# LDO.net
KiCad netlist of a schematic drawn in Altium Designer
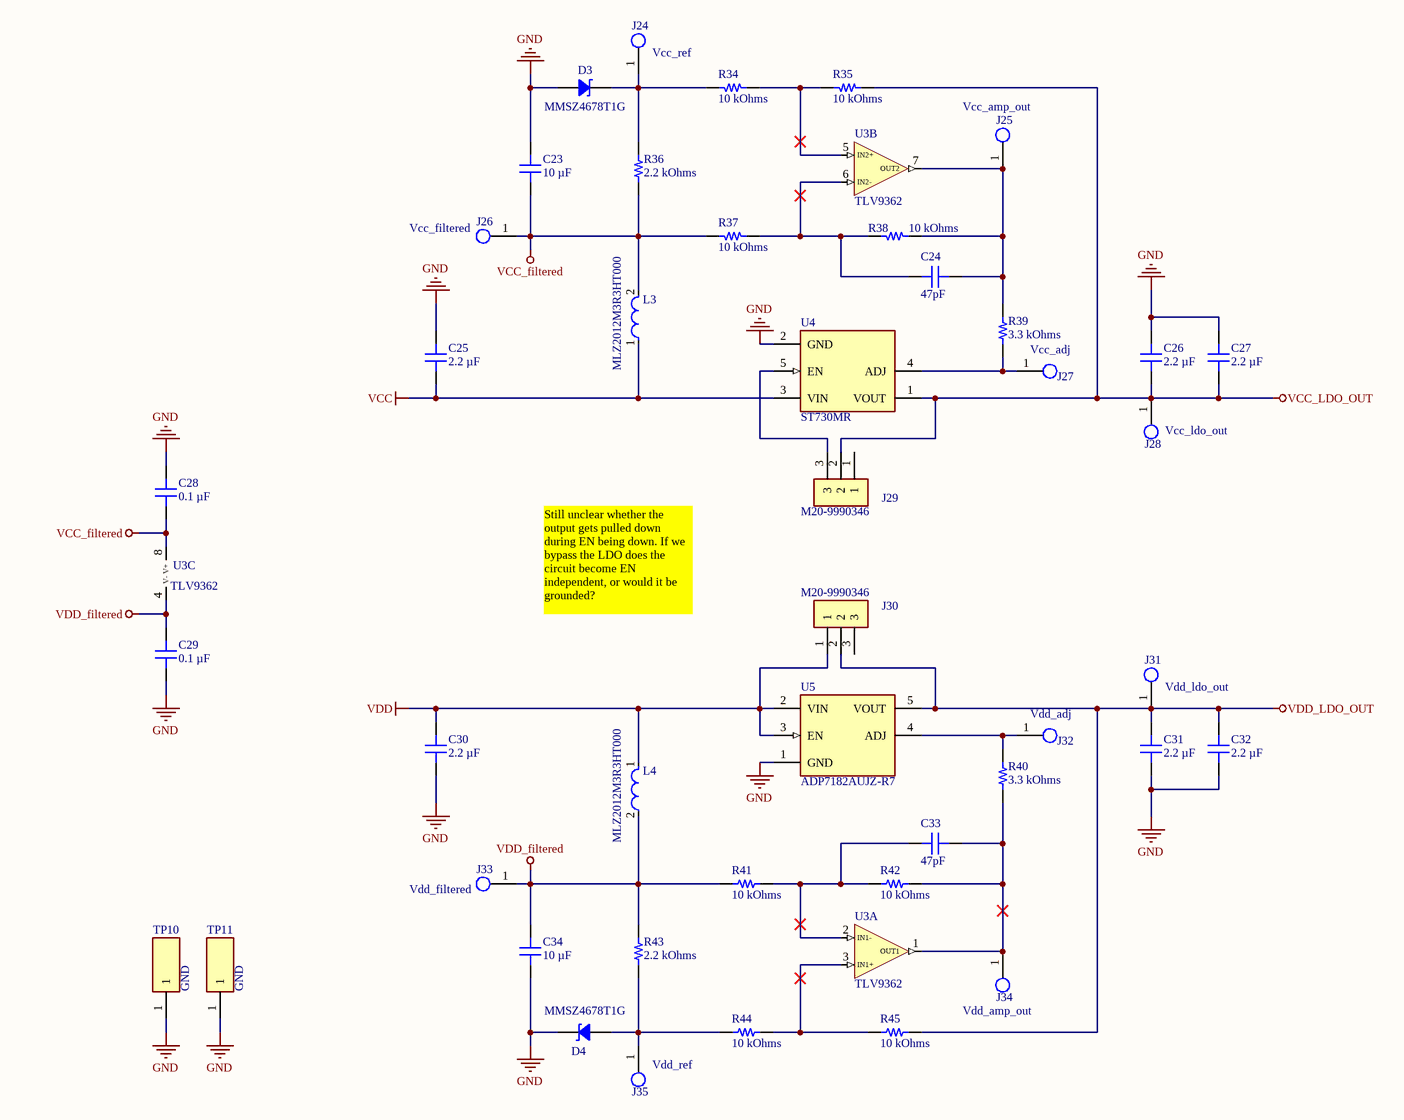
[diagram p0: LDO.SchDoc]

(export (version "E")
  (design (tool "Eeschema 10.0.6"))
  (components
    (comp (ref "C23")
      (value "10 µF")
      (footprint "CAP 1206_3216 - 0.8MM")
      (description "CAP CER 10UF 25V X7R 1206")
      (fields
        (field (name "PART NUMBER") "885012208069")
        (field (name "CAPACITANCE") "10 µF")
        (field (name "MANUFACTURER") "Würth Elektronik")
      )
      (libsource (lib "Celestial Altium Library - altium_library") (part "Capacitor"))
    )
    (comp (ref "C24")
      (value "47pF")
      (footprint "CAP 1206_3216 - 1.8MM")
      (description "CAP CER 47PF 1KV C0G/NP0 1206")
      (fields
        (field (name "PART NUMBER") "1206AA470KAT1A")
        (field (name "CAPACITANCE") "47pF")
        (field (name "MANUFACTURER") "AVX Corporation")
      )
      (libsource (lib "Celestial Altium Library - altium_library") (part "Capacitor"))
    )
    (comp (ref "C25")
      (value "2.2 µF")
      (footprint "CAP 1206_3216 - 0.8MM")
      (description "CAP CER 2.2UF 25V X7R 1206")
      (fields
        (field (name "PART NUMBER") "885382208001")
        (field (name "CAPACITANCE") "2.2 µF")
        (field (name "MANUFACTURER") "Würth Elektronik")
      )
      (libsource (lib "Celestial Altium Library - altium_library") (part "Capacitor"))
    )
    (comp (ref "C26")
      (value "2.2 µF")
      (footprint "CAP 1206_3216 - 0.8MM")
      (description "CAP CER 2.2UF 25V X7R 1206")
      (fields
        (field (name "PART NUMBER") "885382208001")
        (field (name "CAPACITANCE") "2.2 µF")
        (field (name "MANUFACTURER") "Würth Elektronik")
      )
      (libsource (lib "Celestial Altium Library - altium_library") (part "Capacitor"))
    )
    (comp (ref "C27")
      (value "2.2 µF")
      (footprint "CAP 1206_3216 - 0.8MM")
      (description "CAP CER 2.2UF 25V X7R 1206")
      (fields
        (field (name "PART NUMBER") "885382208001")
        (field (name "CAPACITANCE") "2.2 µF")
        (field (name "MANUFACTURER") "Würth Elektronik")
      )
      (libsource (lib "Celestial Altium Library - altium_library") (part "Capacitor"))
    )
    (comp (ref "C28")
      (value "0.1 µF")
      (footprint "CAP 1206_3216 - 0.8MM")
      (description "CAP CER 0.1UF 50V X7R 1206")
      (fields
        (field (name "PART NUMBER") "885012208087")
        (field (name "CAPACITANCE") "0.1 µF")
        (field (name "MANUFACTURER") "Würth Elektronik")
      )
      (libsource (lib "Celestial Altium Library - altium_library") (part "Capacitor"))
    )
    (comp (ref "C29")
      (value "0.1 µF")
      (footprint "CAP 1206_3216 - 0.8MM")
      (description "CAP CER 0.1UF 50V X7R 1206")
      (fields
        (field (name "PART NUMBER") "885012208087")
        (field (name "CAPACITANCE") "0.1 µF")
        (field (name "MANUFACTURER") "Würth Elektronik")
      )
      (libsource (lib "Celestial Altium Library - altium_library") (part "Capacitor"))
    )
    (comp (ref "C30")
      (value "2.2 µF")
      (footprint "CAP 1206_3216 - 0.8MM")
      (description "CAP CER 2.2UF 25V X7R 1206")
      (fields
        (field (name "PART NUMBER") "885382208001")
        (field (name "CAPACITANCE") "2.2 µF")
        (field (name "MANUFACTURER") "Würth Elektronik")
      )
      (libsource (lib "Celestial Altium Library - altium_library") (part "Capacitor"))
    )
    (comp (ref "C31")
      (value "2.2 µF")
      (footprint "CAP 1206_3216 - 0.8MM")
      (description "CAP CER 2.2UF 25V X7R 1206")
      (fields
        (field (name "PART NUMBER") "885382208001")
        (field (name "CAPACITANCE") "2.2 µF")
        (field (name "MANUFACTURER") "Würth Elektronik")
      )
      (libsource (lib "Celestial Altium Library - altium_library") (part "Capacitor"))
    )
    (comp (ref "C32")
      (value "2.2 µF")
      (footprint "CAP 1206_3216 - 0.8MM")
      (description "CAP CER 2.2UF 25V X7R 1206")
      (fields
        (field (name "PART NUMBER") "885382208001")
        (field (name "CAPACITANCE") "2.2 µF")
        (field (name "MANUFACTURER") "Würth Elektronik")
      )
      (libsource (lib "Celestial Altium Library - altium_library") (part "Capacitor"))
    )
    (comp (ref "C33")
      (value "47pF")
      (footprint "CAP 1206_3216 - 1.8MM")
      (description "CAP CER 47PF 1KV C0G/NP0 1206")
      (fields
        (field (name "PART NUMBER") "1206AA470KAT1A")
        (field (name "CAPACITANCE") "47pF")
        (field (name "MANUFACTURER") "AVX Corporation")
      )
      (libsource (lib "Celestial Altium Library - altium_library") (part "Capacitor"))
    )
    (comp (ref "C34")
      (value "10 µF")
      (footprint "CAP 1206_3216 - 0.8MM")
      (description "CAP CER 10UF 25V X7R 1206")
      (fields
        (field (name "PART NUMBER") "885012208069")
        (field (name "CAPACITANCE") "10 µF")
        (field (name "MANUFACTURER") "Würth Elektronik")
      )
      (libsource (lib "Celestial Altium Library - altium_library") (part "Capacitor"))
    )
    (comp (ref "D3")
      (value "MMSZ4678T1G")
      (footprint "SOD3716X135N")
      (description "Zener Diode")
      (fields (field (name "MOUSER PART NUMBER") "863-MMSZ4678T1G"))
      (libsource (lib "za_koncar") (part "MMSZ4678T1G"))
    )
    (comp (ref "D4")
      (value "MMSZ4678T1G")
      (footprint "SOD3716X135N")
      (description "Zener Diode")
      (fields (field (name "MOUSER PART NUMBER") "863-MMSZ4678T1G"))
      (libsource (lib "za_koncar") (part "MMSZ4678T1G"))
    )
    (comp (ref "J24")
      (value "Vcc_ref")
      (footprint "FP-5001-MFG")
      (description "PC TEST POINT MINIATURE BLACK")
      (libsource (lib "za_koncar") (part "5001"))
    )
    (comp (ref "J25")
      (value "Vcc_amp_out")
      (footprint "FP-5001-MFG")
      (description "PC TEST POINT MINIATURE BLACK")
      (libsource (lib "za_koncar") (part "5001"))
    )
    (comp (ref "J26")
      (value "Vcc_filtered")
      (footprint "FP-5001-MFG")
      (description "PC TEST POINT MINIATURE BLACK")
      (libsource (lib "za_koncar") (part "5001"))
    )
    (comp (ref "J27")
      (value "Vcc_adj")
      (footprint "FP-5001-MFG")
      (description "PC TEST POINT MINIATURE BLACK")
      (libsource (lib "za_koncar") (part "5001"))
    )
    (comp (ref "J28")
      (value "Vcc_ldo_out")
      (footprint "FP-5001-MFG")
      (description "PC TEST POINT MINIATURE BLACK")
      (libsource (lib "za_koncar") (part "5001"))
    )
    (comp (ref "J29")
      (value "M20-9990346")
      (footprint "HDRV3W64P0X254_1X3_762X254X864P - duplicate")
      (description "Connector")
      (fields (field (name "MOUSER PART NUMBER") "855-M20-9990346"))
      (libsource (lib "za_koncar") (part "M20-9990346"))
    )
    (comp (ref "J30")
      (value "M20-9990346")
      (footprint "HDRV3W64P0X254_1X3_762X254X864P - duplicate")
      (description "Connector")
      (fields (field (name "MOUSER PART NUMBER") "855-M20-9990346"))
      (libsource (lib "") (part "M20-9990346_1"))
    )
    (comp (ref "J31")
      (value "Vdd_ldo_out")
      (footprint "FP-5001-MFG")
      (description "PC TEST POINT MINIATURE BLACK")
      (libsource (lib "za_koncar") (part "5001"))
    )
    (comp (ref "J32")
      (value "Vdd_adj")
      (footprint "FP-5001-MFG")
      (description "PC TEST POINT MINIATURE BLACK")
      (libsource (lib "za_koncar") (part "5001"))
    )
    (comp (ref "J33")
      (value "Vdd_filtered")
      (footprint "FP-5001-MFG")
      (description "PC TEST POINT MINIATURE BLACK")
      (libsource (lib "za_koncar") (part "5001"))
    )
    (comp (ref "J34")
      (value "Vdd_amp_out")
      (footprint "FP-5001-MFG")
      (description "PC TEST POINT MINIATURE BLACK")
      (libsource (lib "za_koncar") (part "5001"))
    )
    (comp (ref "J35")
      (value "Vdd_ref")
      (footprint "FP-5001-MFG")
      (description "PC TEST POINT MINIATURE BLACK")
      (libsource (lib "za_koncar") (part "5001"))
    )
    (comp (ref "L3")
      (value "MLZ2012M3R3HT000")
      (footprint "FP-MLZ2012-1_25-IPC_B")
      (description "Shielded Multilayer Inductor 3.3uH ±20% 500mA 260mΩ SMD 0805")
      (fields (field (name "TOLERANCE") "20%"))
      (libsource (lib "za_koncar") (part "MLZ2012M3R3HT000"))
    )
    (comp (ref "L4")
      (value "MLZ2012M3R3HT000")
      (footprint "FP-MLZ2012-1_25-IPC_B")
      (description "Shielded Multilayer Inductor 3.3uH ±20% 500mA 260mΩ SMD 0805")
      (fields (field (name "TOLERANCE") "20%"))
      (libsource (lib "") (part "MLZ2012M3R3HT000_1"))
    )
    (comp (ref "R34")
      (value "10 kOhms")
      (footprint "YAGEO RES 1206_3216")
      (description "RES SMD 10K OHM 1% 1/4W 1206")
      (fields (field (name "PART NUMBER") "RT1206FRE0710KL") (field (name "MANUFACTURER") "Yageo"))
      (libsource (lib "Celestial Altium Library - altium_library") (part "Resistor"))
    )
    (comp (ref "R35")
      (value "10 kOhms")
      (footprint "YAGEO RES 1206_3216")
      (description "RES SMD 10K OHM 1% 1/4W 1206")
      (fields (field (name "PART NUMBER") "RT1206FRE0710KL") (field (name "MANUFACTURER") "Yageo"))
      (libsource (lib "Celestial Altium Library - altium_library") (part "Resistor"))
    )
    (comp (ref "R36")
      (value "2.2 kOhms")
      (footprint "YAGEO RES 1206_3216")
      (description "RES SMD 2.2K OHM 1% 1/4W 1206")
      (fields (field (name "PART NUMBER") "RT1206FRE072K2L") (field (name "MANUFACTURER") "Yageo"))
      (libsource (lib "Celestial Altium Library - altium_library") (part "Resistor"))
    )
    (comp (ref "R37")
      (value "10 kOhms")
      (footprint "YAGEO RES 1206_3216")
      (description "RES SMD 10K OHM 1% 1/4W 1206")
      (fields (field (name "PART NUMBER") "RT1206FRE0710KL") (field (name "MANUFACTURER") "Yageo"))
      (libsource (lib "Celestial Altium Library - altium_library") (part "Resistor"))
    )
    (comp (ref "R38")
      (value "10 kOhms")
      (footprint "YAGEO RES 1206_3216")
      (description "RES SMD 10K OHM 1% 1/4W 1206")
      (fields (field (name "PART NUMBER") "RT1206FRE0710KL") (field (name "MANUFACTURER") "Yageo"))
      (libsource (lib "Celestial Altium Library - altium_library") (part "Resistor"))
    )
    (comp (ref "R39")
      (value "3.3 kOhms")
      (footprint "YAGEO RES 1206_3216")
      (description "RES SMD 3.3K OHM 1% 1/4W 1206")
      (fields (field (name "PART NUMBER") "RT1206FRE073K3L") (field (name "MANUFACTURER") "Yageo"))
      (libsource (lib "Celestial Altium Library - altium_library") (part "Resistor"))
    )
    (comp (ref "R40")
      (value "3.3 kOhms")
      (footprint "YAGEO RES 1206_3216")
      (description "RES SMD 3.3K OHM 1% 1/4W 1206")
      (fields (field (name "PART NUMBER") "RT1206FRE073K3L") (field (name "MANUFACTURER") "Yageo"))
      (libsource (lib "Celestial Altium Library - altium_library") (part "Resistor"))
    )
    (comp (ref "R41")
      (value "10 kOhms")
      (footprint "YAGEO RES 1206_3216")
      (description "RES SMD 10K OHM 1% 1/4W 1206")
      (fields (field (name "PART NUMBER") "RT1206FRE0710KL") (field (name "MANUFACTURER") "Yageo"))
      (libsource (lib "Celestial Altium Library - altium_library") (part "Resistor"))
    )
    (comp (ref "R42")
      (value "10 kOhms")
      (footprint "YAGEO RES 1206_3216")
      (description "RES SMD 10K OHM 1% 1/4W 1206")
      (fields (field (name "PART NUMBER") "RT1206FRE0710KL") (field (name "MANUFACTURER") "Yageo"))
      (libsource (lib "Celestial Altium Library - altium_library") (part "Resistor"))
    )
    (comp (ref "R43")
      (value "2.2 kOhms")
      (footprint "YAGEO RES 1206_3216")
      (description "RES SMD 2.2K OHM 1% 1/4W 1206")
      (fields (field (name "PART NUMBER") "RT1206FRE072K2L") (field (name "MANUFACTURER") "Yageo"))
      (libsource (lib "Celestial Altium Library - altium_library") (part "Resistor"))
    )
    (comp (ref "R44")
      (value "10 kOhms")
      (footprint "YAGEO RES 1206_3216")
      (description "RES SMD 10K OHM 1% 1/4W 1206")
      (fields (field (name "PART NUMBER") "RT1206FRE0710KL") (field (name "MANUFACTURER") "Yageo"))
      (libsource (lib "Celestial Altium Library - altium_library") (part "Resistor"))
    )
    (comp (ref "R45")
      (value "10 kOhms")
      (footprint "YAGEO RES 1206_3216")
      (description "RES SMD 10K OHM 1% 1/4W 1206")
      (fields (field (name "PART NUMBER") "RT1206FRE0710KL") (field (name "MANUFACTURER") "Yageo"))
      (libsource (lib "Celestial Altium Library - altium_library") (part "Resistor"))
    )
    (comp (ref "TP10")
      (value "GND")
      (footprint "za_koncar:S175146R")
      (description "Test Point")
      (fields
        (field (name "MANUFACTURER_PART_NUMBER") "S1751-46R")
        (field (name "MOUSER PART NUMBER") "855-S1751-46R")
      )
      (libsource (lib "za_koncar") (part "S1751-46R"))
    )
    (comp (ref "TP11")
      (value "GND")
      (footprint "za_koncar:S175146R")
      (description "Test Point")
      (fields
        (field (name "MANUFACTURER_PART_NUMBER") "S1751-46R")
        (field (name "MOUSER PART NUMBER") "855-S1751-46R")
      )
      (libsource (lib "za_koncar") (part "S1751-46R"))
    )
    (comp (ref "U3")
      (value "TLV9362")
      (footprint "SOIC8-127P600X175-8N")
      (description "TLV936x 10-MHz, 40-V, RRO, Operational Amplifie")
      (libsource (lib "za_koncar") (part "TLV9362"))
    )
    (comp (ref "U4")
      (value "ST730MR")
      (footprint "FP-UJ-5-IPC_B")
      (libsource (lib "za_koncar") (part "ST730MR"))
    )
    (comp (ref "U5")
      (value "ADP7182AUJZ-R7")
      (footprint "FP-UJ-5-IPC_B")
      (description "IC REG LIN NEG ADJ 200MA 5TSOT")
      (fields
        (field (name "MANUFACTURER") "Analog Devices")
        (field (name "OCTOPART") "https://octopart.com/adp7182aujz-r7-analog+devices-21054665")
      )
      (libsource (lib "za_koncar") (part "ADP7182"))
    )
  )
  (nets
    (net (code "1") (name "GND") (class "Default")
      (node (ref "C23") (pin "1") (pinfunction "1_1") (pintype "passive"))
      (node (ref "C25") (pin "1") (pinfunction "1_1") (pintype "passive"))
      (node (ref "C26") (pin "1") (pinfunction "1_1") (pintype "passive"))
      (node (ref "C27") (pin "1") (pinfunction "1_1") (pintype "passive"))
      (node (ref "C28") (pin "2") (pinfunction "2_2") (pintype "passive"))
      (node (ref "C29") (pin "1") (pinfunction "1_1") (pintype "passive"))
      (node (ref "C30") (pin "1") (pinfunction "1_1") (pintype "passive"))
      (node (ref "C31") (pin "1") (pinfunction "1_1") (pintype "passive"))
      (node (ref "C32") (pin "1") (pinfunction "1_1") (pintype "passive"))
      (node (ref "C34") (pin "1") (pinfunction "1_1") (pintype "passive"))
      (node (ref "D3") (pin "1") (pinfunction "1_1") (pintype "passive"))
      (node (ref "D4") (pin "2") (pinfunction "2_2") (pintype "passive"))
      (node (ref "TP10") (pin "1") (pinfunction "1_1") (pintype "passive"))
      (node (ref "TP11") (pin "1") (pinfunction "1_1") (pintype "passive"))
      (node (ref "U4") (pin "2") (pinfunction "GND_2") (pintype "power_in"))
      (node (ref "U5") (pin "1") (pinfunction "GND_1") (pintype "power_in"))
    )
    (net (code "2") (name "Net-(D3-Pad2)") (class "Default")
      (node (ref "D3") (pin "2") (pinfunction "2_2") (pintype "passive"))
      (node (ref "J24") (pin "1") (pinfunction "1_1") (pintype "passive"))
      (node (ref "R34") (pin "2") (pinfunction "2_2") (pintype "passive"))
      (node (ref "R36") (pin "2") (pinfunction "2_2") (pintype "passive"))
    )
    (net (code "3") (name "Net-(D4-Pad1)") (class "Default")
      (node (ref "D4") (pin "1") (pinfunction "1_1") (pintype "passive"))
      (node (ref "J35") (pin "1") (pinfunction "1_1") (pintype "passive"))
      (node (ref "R43") (pin "1") (pinfunction "1_1") (pintype "passive"))
      (node (ref "R44") (pin "2") (pinfunction "2_2") (pintype "passive"))
    )
    (net (code "4") (name "Net-(U3A-IN1+)") (class "Default")
      (node (ref "R44") (pin "1") (pinfunction "1_1") (pintype "passive"))
      (node (ref "R45") (pin "2") (pinfunction "2_2") (pintype "passive"))
      (node (ref "U3") (pin "3") (pinfunction "IN1+_3") (pintype "input"))
    )
    (net (code "5") (name "Net-(U3A-IN1-)") (class "Default")
      (node (ref "C33") (pin "1") (pinfunction "1_1") (pintype "passive"))
      (node (ref "R41") (pin "1") (pinfunction "1_1") (pintype "passive"))
      (node (ref "R42") (pin "2") (pinfunction "2_2") (pintype "passive"))
      (node (ref "U3") (pin "2") (pinfunction "IN1-_2") (pintype "input"))
    )
    (net (code "6") (name "Net-(U3A-OUT1)") (class "Default")
      (node (ref "C33") (pin "2") (pinfunction "2_2") (pintype "passive"))
      (node (ref "J34") (pin "1") (pinfunction "1_1") (pintype "passive"))
      (node (ref "R40") (pin "2") (pinfunction "2_2") (pintype "passive"))
      (node (ref "R42") (pin "1") (pinfunction "1_1") (pintype "passive"))
      (node (ref "U3") (pin "1") (pinfunction "OUT1_1") (pintype "output"))
    )
    (net (code "7") (name "Net-(U3B-IN2+)") (class "Default")
      (node (ref "R34") (pin "1") (pinfunction "1_1") (pintype "passive"))
      (node (ref "R35") (pin "2") (pinfunction "2_2") (pintype "passive"))
      (node (ref "U3") (pin "5") (pinfunction "IN2+_5") (pintype "input"))
    )
    (net (code "8") (name "Net-(U3B-IN2-)") (class "Default")
      (node (ref "C24") (pin "1") (pinfunction "1_1") (pintype "passive"))
      (node (ref "R37") (pin "1") (pinfunction "1_1") (pintype "passive"))
      (node (ref "R38") (pin "2") (pinfunction "2_2") (pintype "passive"))
      (node (ref "U3") (pin "6") (pinfunction "IN2-_6") (pintype "input"))
    )
    (net (code "9") (name "Net-(U3B-OUT2)") (class "Default")
      (node (ref "C24") (pin "2") (pinfunction "2_2") (pintype "passive"))
      (node (ref "J25") (pin "1") (pinfunction "1_1") (pintype "passive"))
      (node (ref "R38") (pin "1") (pinfunction "1_1") (pintype "passive"))
      (node (ref "R39") (pin "1") (pinfunction "1_1") (pintype "passive"))
      (node (ref "U3") (pin "7") (pinfunction "OUT2_7") (pintype "output"))
    )
    (net (code "10") (name "Net-(U4-ADJ)") (class "Default")
      (node (ref "J27") (pin "1") (pinfunction "1_1") (pintype "passive"))
      (node (ref "R39") (pin "2") (pinfunction "2_2") (pintype "passive"))
      (node (ref "U4") (pin "4") (pinfunction "ADJ_4") (pintype "passive"))
    )
    (net (code "11") (name "Net-(U4-EN)") (class "Default")
      (node (ref "J29") (pin "3") (pinfunction "3_3") (pintype "passive"))
      (node (ref "U4") (pin "5") (pinfunction "EN_5") (pintype "input"))
    )
    (net (code "12") (name "Net-(U5-ADJ)") (class "Default")
      (node (ref "J32") (pin "1") (pinfunction "1_1") (pintype "passive"))
      (node (ref "R40") (pin "1") (pinfunction "1_1") (pintype "passive"))
      (node (ref "U5") (pin "4") (pinfunction "ADJ_4") (pintype "passive"))
    )
    (net (code "13") (name "VCC") (class "Default")
      (node (ref "C25") (pin "2") (pinfunction "2_2") (pintype "passive"))
      (node (ref "L3") (pin "1") (pinfunction "1_1") (pintype "passive"))
      (node (ref "U4") (pin "3") (pinfunction "VIN_3") (pintype "power_in"))
    )
    (net (code "14") (name "VCC_LDO_OUT") (class "Default")
      (node (ref "C26") (pin "2") (pinfunction "2_2") (pintype "passive"))
      (node (ref "C27") (pin "2") (pinfunction "2_2") (pintype "passive"))
      (node (ref "J28") (pin "1") (pinfunction "1_1") (pintype "passive"))
      (node (ref "J29") (pin "2") (pinfunction "2_2") (pintype "passive"))
      (node (ref "R35") (pin "1") (pinfunction "1_1") (pintype "passive"))
      (node (ref "U4") (pin "1") (pinfunction "VOUT_1") (pintype "power_in"))
    )
    (net (code "15") (name "VCC_filtered") (class "Default")
      (node (ref "C23") (pin "2") (pinfunction "2_2") (pintype "passive"))
      (node (ref "C28") (pin "1") (pinfunction "1_1") (pintype "passive"))
      (node (ref "J26") (pin "1") (pinfunction "1_1") (pintype "passive"))
      (node (ref "L3") (pin "2") (pinfunction "2_2") (pintype "passive"))
      (node (ref "R36") (pin "1") (pinfunction "1_1") (pintype "passive"))
      (node (ref "R37") (pin "2") (pinfunction "2_2") (pintype "passive"))
      (node (ref "U3") (pin "8") (pinfunction "V+_8") (pintype "power_in"))
    )
    (net (code "16") (name "VDD") (class "Default")
      (node (ref "C30") (pin "2") (pinfunction "2_2") (pintype "passive"))
      (node (ref "J30") (pin "1") (pinfunction "1_1") (pintype "passive"))
      (node (ref "L4") (pin "1") (pinfunction "1_1") (pintype "passive"))
      (node (ref "U5") (pin "2") (pinfunction "VIN_2") (pintype "power_in"))
      (node (ref "U5") (pin "3") (pinfunction "EN_3") (pintype "input"))
    )
    (net (code "17") (name "VDD_LDO_OUT") (class "Default")
      (node (ref "C31") (pin "2") (pinfunction "2_2") (pintype "passive"))
      (node (ref "C32") (pin "2") (pinfunction "2_2") (pintype "passive"))
      (node (ref "J30") (pin "2") (pinfunction "2_2") (pintype "passive"))
      (node (ref "J31") (pin "1") (pinfunction "1_1") (pintype "passive"))
      (node (ref "R45") (pin "1") (pinfunction "1_1") (pintype "passive"))
      (node (ref "U5") (pin "5") (pinfunction "VOUT_5") (pintype "power_in"))
    )
    (net (code "18") (name "VDD_filtered") (class "Default")
      (node (ref "C29") (pin "2") (pinfunction "2_2") (pintype "passive"))
      (node (ref "C34") (pin "2") (pinfunction "2_2") (pintype "passive"))
      (node (ref "J33") (pin "1") (pinfunction "1_1") (pintype "passive"))
      (node (ref "L4") (pin "2") (pinfunction "2_2") (pintype "passive"))
      (node (ref "R41") (pin "2") (pinfunction "2_2") (pintype "passive"))
      (node (ref "R43") (pin "2") (pinfunction "2_2") (pintype "passive"))
      (node (ref "U3") (pin "4") (pinfunction "V-_4") (pintype "power_in"))
    )
    (net (code "19") (name "unconnected-(J29-Pad1)") (class "Default")
      (node (ref "J29") (pin "1") (pinfunction "1_1") (pintype "passive"))
    )
    (net (code "20") (name "unconnected-(J30-Pad3)") (class "Default")
      (node (ref "J30") (pin "3") (pinfunction "3_3") (pintype "passive"))
    )
  )
)
